# mp3triggerv3.net
KiCad netlist of a schematic drawn in EAGLE
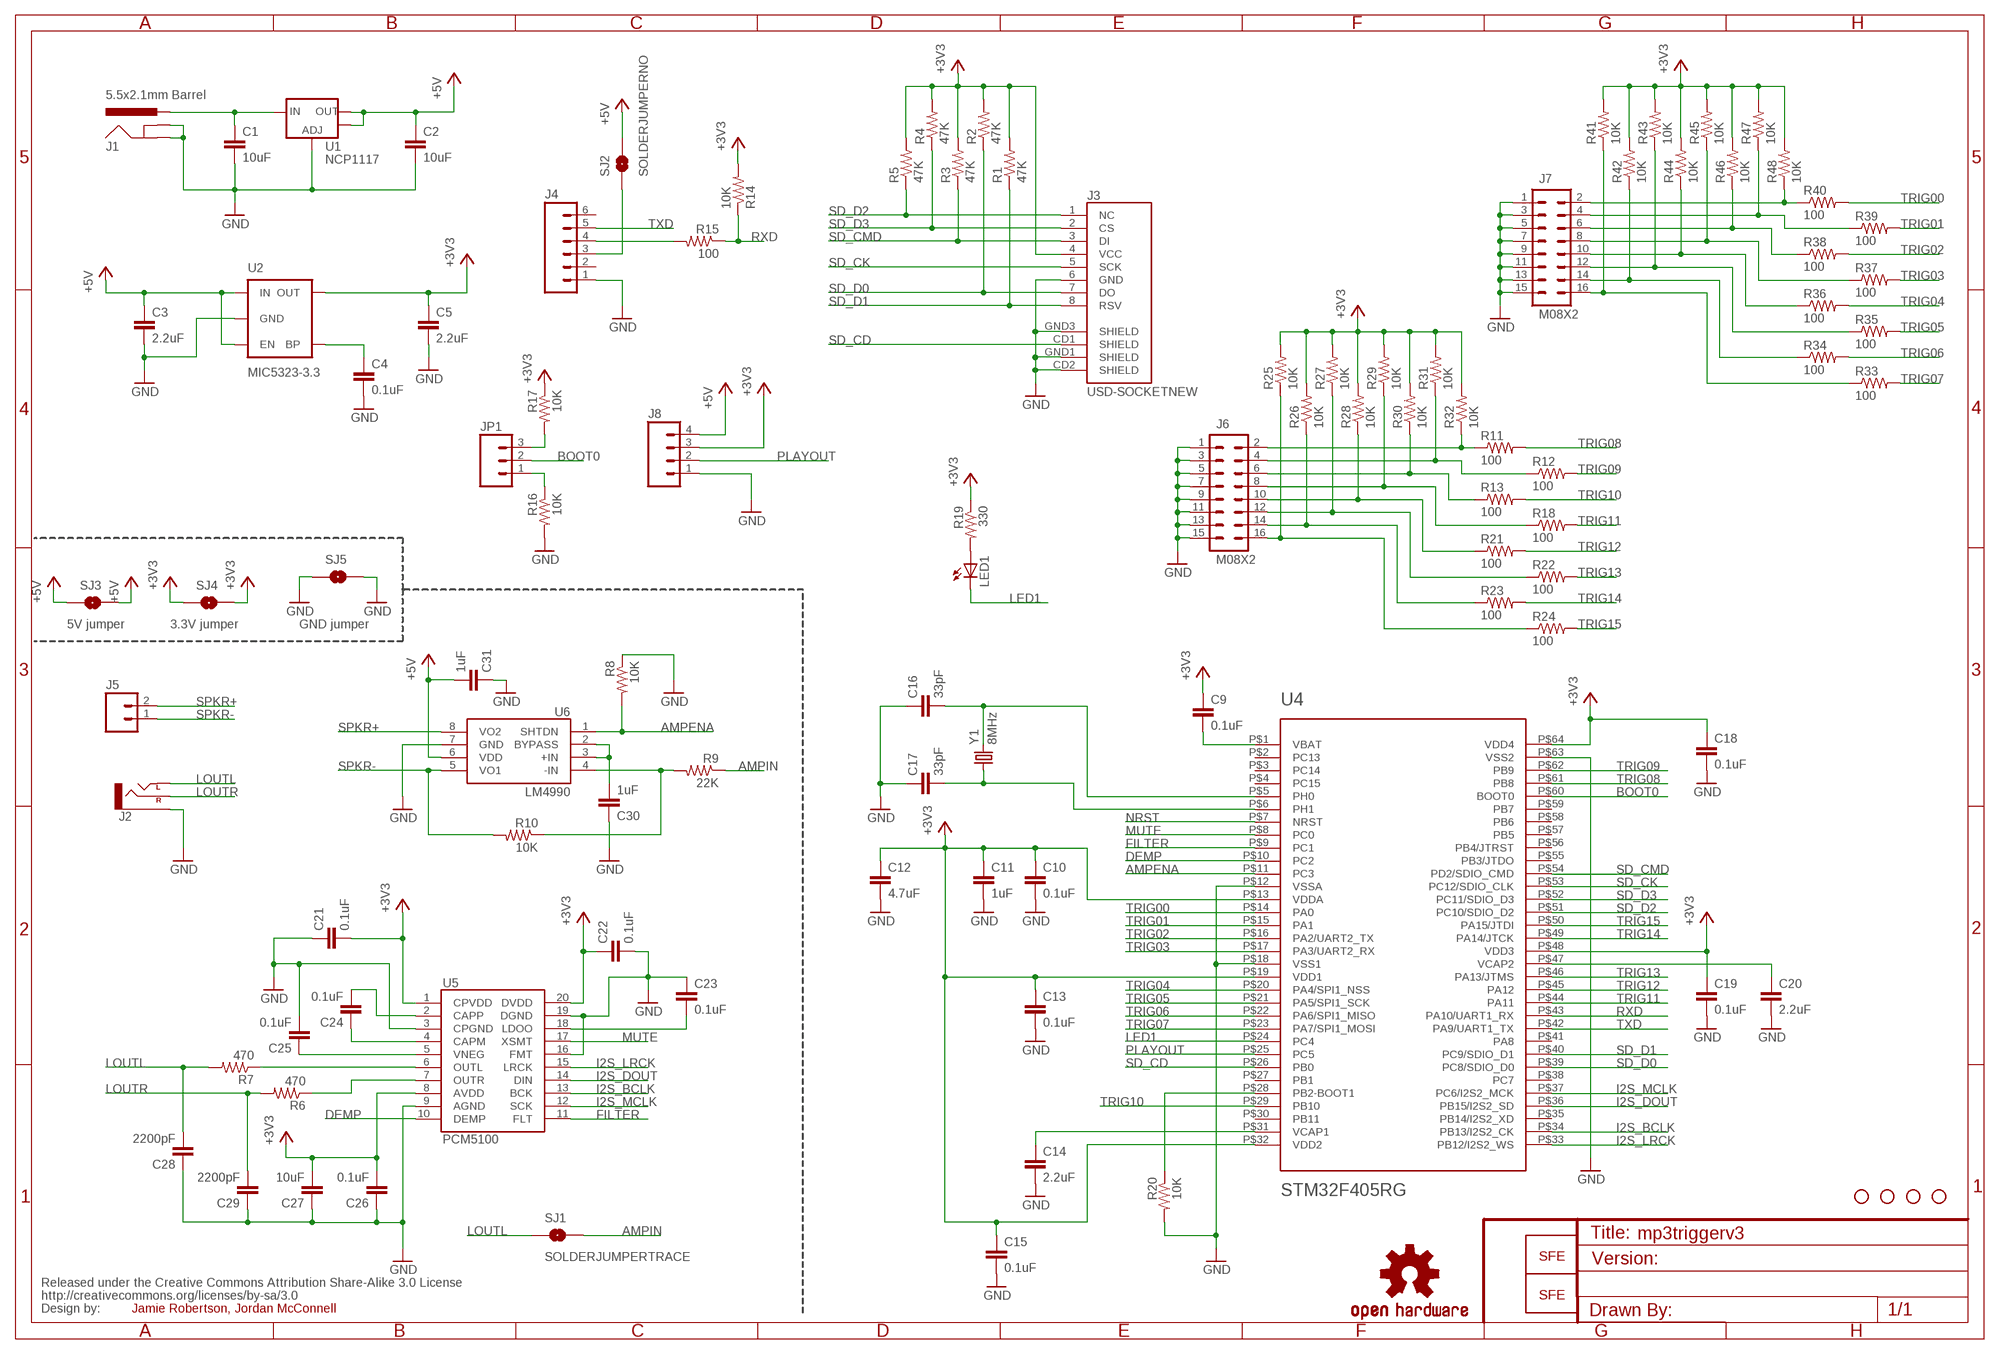
[diagram p0: schematic, sheet 1]

(export (version "E")
  (design (tool "Eeschema 10.0.6"))
  (components
    (comp (ref "C1")
      (value "10uF")
      (footprint "eagle-import:1210")
      (libsource (lib "eagle-import") (part "10UF50V20%(1210)"))
    )
    (comp (ref "C2")
      (value "10uF")
      (footprint "eagle-import:0805")
      (libsource (lib "eagle-import") (part "1UF-25V-10%(0805)"))
    )
    (comp (ref "C3")
      (value "2.2uF")
      (footprint "eagle-import:0805")
      (libsource (lib "eagle-import") (part "1UF-25V-10%(0805)"))
    )
    (comp (ref "C4")
      (value "0.1uF")
      (footprint "eagle-import:0603-CAP")
      (libsource (lib "eagle-import") (part "CAP0603-CAP"))
    )
    (comp (ref "C5")
      (value "2.2uF")
      (footprint "eagle-import:0805")
      (libsource (lib "eagle-import") (part "1UF-25V-10%(0805)"))
    )
    (comp (ref "C9")
      (value "0.1uF")
      (footprint "eagle-import:0603-CAP")
      (libsource (lib "eagle-import") (part "CAP0603-CAP"))
    )
    (comp (ref "C10")
      (value "0.1uF")
      (footprint "eagle-import:0603-CAP")
      (libsource (lib "eagle-import") (part "CAP0603-CAP"))
    )
    (comp (ref "C11")
      (value "1uF")
      (footprint "eagle-import:0603-CAP")
      (libsource (lib "eagle-import") (part "CAP0603-CAP"))
    )
    (comp (ref "C12")
      (value "4.7uF")
      (footprint "eagle-import:0603-CAP")
      (libsource (lib "eagle-import") (part "CAP0603-CAP"))
    )
    (comp (ref "C13")
      (value "0.1uF")
      (footprint "eagle-import:0603-CAP")
      (libsource (lib "eagle-import") (part "CAP0603-CAP"))
    )
    (comp (ref "C14")
      (value "2.2uF")
      (footprint "eagle-import:0603-CAP")
      (libsource (lib "eagle-import") (part "CAP0603-CAP"))
    )
    (comp (ref "C15")
      (value "0.1uF")
      (footprint "eagle-import:0603-CAP")
      (libsource (lib "eagle-import") (part "CAP0603-CAP"))
    )
    (comp (ref "C16")
      (value "33pF")
      (footprint "eagle-import:0603-CAP")
      (libsource (lib "eagle-import") (part "CAP0603-CAP"))
    )
    (comp (ref "C17")
      (value "33pF")
      (footprint "eagle-import:0603-CAP")
      (libsource (lib "eagle-import") (part "CAP0603-CAP"))
    )
    (comp (ref "C18")
      (value "0.1uF")
      (footprint "eagle-import:0603-CAP")
      (libsource (lib "eagle-import") (part "CAP0603-CAP"))
    )
    (comp (ref "C19")
      (value "0.1uF")
      (footprint "eagle-import:0603-CAP")
      (libsource (lib "eagle-import") (part "CAP0603-CAP"))
    )
    (comp (ref "C20")
      (value "2.2uF")
      (footprint "eagle-import:0603-CAP")
      (libsource (lib "eagle-import") (part "CAP0603-CAP"))
    )
    (comp (ref "C21")
      (value "0.1uF")
      (footprint "eagle-import:0603-CAP")
      (libsource (lib "eagle-import") (part "CAP0603-CAP"))
    )
    (comp (ref "C22")
      (value "0.1uF")
      (footprint "eagle-import:0603-CAP")
      (libsource (lib "eagle-import") (part "CAP0603-CAP"))
    )
    (comp (ref "C23")
      (value "0.1uF")
      (footprint "eagle-import:0603-CAP")
      (libsource (lib "eagle-import") (part "CAP0603-CAP"))
    )
    (comp (ref "C24")
      (value "0.1uF")
      (footprint "eagle-import:0603-CAP")
      (libsource (lib "eagle-import") (part "CAP0603-CAP"))
    )
    (comp (ref "C25")
      (value "0.1uF")
      (footprint "eagle-import:0603-CAP")
      (libsource (lib "eagle-import") (part "CAP0603-CAP"))
    )
    (comp (ref "C26")
      (value "0.1uF")
      (footprint "eagle-import:0603-CAP")
      (libsource (lib "eagle-import") (part "CAP0603-CAP"))
    )
    (comp (ref "C27")
      (value "10uF")
      (footprint "eagle-import:0603-CAP")
      (libsource (lib "eagle-import") (part "CAP0603-CAP"))
    )
    (comp (ref "C28")
      (value "2200pF")
      (footprint "eagle-import:0603-CAP")
      (libsource (lib "eagle-import") (part "CAP0603-CAP"))
    )
    (comp (ref "C29")
      (value "2200pF")
      (footprint "eagle-import:0603-CAP")
      (libsource (lib "eagle-import") (part "CAP0603-CAP"))
    )
    (comp (ref "C30")
      (value "1uF")
      (footprint "eagle-import:0603-CAP")
      (libsource (lib "eagle-import") (part "CAP0603-CAP"))
    )
    (comp (ref "C31")
      (value "1uF")
      (footprint "eagle-import:0603-CAP")
      (libsource (lib "eagle-import") (part "CAP0603-CAP"))
    )
    (comp (ref "CC_TEXT1")
      (value "CREATIVE_COMMONS")
      (footprint "eagle-import:CREATIVE_COMMONS")
      (libsource (lib "eagle-import") (part "CREATIVE_COMMONS"))
    )
    (comp (ref "J1")
      (value "5.5x2.1mm Barrel")
      (footprint "eagle-import:POWER_JACK_SMD")
      (libsource (lib "eagle-import") (part "POWER_JACKSMD"))
    )
    (comp (ref "J2")
      (value "AUDIO-JACKSMD2")
      (footprint "eagle-import:AUDIO-JACK-3.5MM-SMD")
      (libsource (lib "eagle-import") (part "AUDIO-JACKSMD2"))
    )
    (comp (ref "J3")
      (value "USD-SOCKETNEW")
      (footprint "eagle-import:MICRO-SD-SOCKET-PP")
      (libsource (lib "eagle-import") (part "USD-SOCKETNEW"))
    )
    (comp (ref "J4")
      (value "M06SIP")
      (footprint "eagle-import:1X06")
      (libsource (lib "eagle-import") (part "M06SIP"))
    )
    (comp (ref "J5")
      (value "M02PTH")
      (footprint "eagle-import:1X02")
      (libsource (lib "eagle-import") (part "M02PTH"))
    )
    (comp (ref "J6")
      (value "M08X2")
      (footprint "eagle-import:2X8")
      (libsource (lib "eagle-import") (part "M08X2"))
    )
    (comp (ref "J7")
      (value "M08X2")
      (footprint "eagle-import:2X8")
      (libsource (lib "eagle-import") (part "M08X2"))
    )
    (comp (ref "J8")
      (value "M04PTH")
      (footprint "eagle-import:1X04")
      (libsource (lib "eagle-import") (part "M04PTH"))
    )
    (comp (ref "JP1")
      (value "M03PTH")
      (footprint "eagle-import:1X03")
      (libsource (lib "eagle-import") (part "M03PTH"))
    )
    (comp (ref "LED1")
      (value "LED0603")
      (footprint "eagle-import:LED-0603")
      (libsource (lib "eagle-import") (part "LED0603"))
    )
    (comp (ref "LOGO1")
      (value "OSHW-LOGOL")
      (footprint "eagle-import:OSHW-LOGO-L")
      (libsource (lib "eagle-import") (part "OSHW-LOGOL"))
    )
    (comp (ref "LOGO2")
      (value "LOGO-SFENEW")
      (footprint "eagle-import:SFE-NEW-WEBLOGO")
      (libsource (lib "eagle-import") (part "LOGO-SFENEW"))
    )
    (comp (ref "LOGO3")
      (value "LOGO-SFESK")
      (footprint "eagle-import:SFE-LOGO-FLAME")
      (libsource (lib "eagle-import") (part "LOGO-SFESK"))
    )
    (comp (ref "R1")
      (value "47K")
      (footprint "eagle-import:0603-RES")
      (libsource (lib "eagle-import") (part "RESISTOR0603-RES"))
    )
    (comp (ref "R2")
      (value "47K")
      (footprint "eagle-import:0603-RES")
      (libsource (lib "eagle-import") (part "RESISTOR0603-RES"))
    )
    (comp (ref "R3")
      (value "47K")
      (footprint "eagle-import:0603-RES")
      (libsource (lib "eagle-import") (part "RESISTOR0603-RES"))
    )
    (comp (ref "R4")
      (value "47K")
      (footprint "eagle-import:0603-RES")
      (libsource (lib "eagle-import") (part "RESISTOR0603-RES"))
    )
    (comp (ref "R5")
      (value "47K")
      (footprint "eagle-import:0603-RES")
      (libsource (lib "eagle-import") (part "RESISTOR0603-RES"))
    )
    (comp (ref "R6")
      (value "470")
      (footprint "eagle-import:0603-RES")
      (libsource (lib "eagle-import") (part "RESISTOR0603-RES"))
    )
    (comp (ref "R7")
      (value "470")
      (footprint "eagle-import:0603-RES")
      (libsource (lib "eagle-import") (part "RESISTOR0603-RES"))
    )
    (comp (ref "R8")
      (value "10K")
      (footprint "eagle-import:0603-RES")
      (libsource (lib "eagle-import") (part "RESISTOR0603-RES"))
    )
    (comp (ref "R9")
      (value "22K")
      (footprint "eagle-import:0603-RES")
      (libsource (lib "eagle-import") (part "RESISTOR0603-RES"))
    )
    (comp (ref "R10")
      (value "10K")
      (footprint "eagle-import:0603-RES")
      (libsource (lib "eagle-import") (part "RESISTOR0603-RES"))
    )
    (comp (ref "R11")
      (value "100")
      (footprint "eagle-import:0603-RES")
      (libsource (lib "eagle-import") (part "RESISTOR0603-RES"))
    )
    (comp (ref "R12")
      (value "100")
      (footprint "eagle-import:0603-RES")
      (libsource (lib "eagle-import") (part "RESISTOR0603-RES"))
    )
    (comp (ref "R13")
      (value "100")
      (footprint "eagle-import:0603-RES")
      (libsource (lib "eagle-import") (part "RESISTOR0603-RES"))
    )
    (comp (ref "R14")
      (value "10K")
      (footprint "eagle-import:0603-RES")
      (libsource (lib "eagle-import") (part "RESISTOR0603-RES"))
    )
    (comp (ref "R15")
      (value "100")
      (footprint "eagle-import:0603-RES")
      (libsource (lib "eagle-import") (part "RESISTOR0603-RES"))
    )
    (comp (ref "R16")
      (value "10K")
      (footprint "eagle-import:0603-RES")
      (libsource (lib "eagle-import") (part "RESISTOR0603-RES"))
    )
    (comp (ref "R17")
      (value "10K")
      (footprint "eagle-import:0603-RES")
      (libsource (lib "eagle-import") (part "RESISTOR0603-RES"))
    )
    (comp (ref "R18")
      (value "100")
      (footprint "eagle-import:0603-RES")
      (libsource (lib "eagle-import") (part "RESISTOR0603-RES"))
    )
    (comp (ref "R19")
      (value "330")
      (footprint "eagle-import:0603-RES")
      (libsource (lib "eagle-import") (part "RESISTOR0603-RES"))
    )
    (comp (ref "R20")
      (value "10K")
      (footprint "eagle-import:0603-RES")
      (libsource (lib "eagle-import") (part "RESISTOR0603-RES"))
    )
    (comp (ref "R21")
      (value "100")
      (footprint "eagle-import:0603-RES")
      (libsource (lib "eagle-import") (part "RESISTOR0603-RES"))
    )
    (comp (ref "R22")
      (value "100")
      (footprint "eagle-import:0603-RES")
      (libsource (lib "eagle-import") (part "RESISTOR0603-RES"))
    )
    (comp (ref "R23")
      (value "100")
      (footprint "eagle-import:0603-RES")
      (libsource (lib "eagle-import") (part "RESISTOR0603-RES"))
    )
    (comp (ref "R24")
      (value "100")
      (footprint "eagle-import:0603-RES")
      (libsource (lib "eagle-import") (part "RESISTOR0603-RES"))
    )
    (comp (ref "R25")
      (value "10K")
      (footprint "eagle-import:0603-RES")
      (libsource (lib "eagle-import") (part "RESISTOR0603-RES"))
    )
    (comp (ref "R26")
      (value "10K")
      (footprint "eagle-import:0603-RES")
      (libsource (lib "eagle-import") (part "RESISTOR0603-RES"))
    )
    (comp (ref "R27")
      (value "10K")
      (footprint "eagle-import:0603-RES")
      (libsource (lib "eagle-import") (part "RESISTOR0603-RES"))
    )
    (comp (ref "R28")
      (value "10K")
      (footprint "eagle-import:0603-RES")
      (libsource (lib "eagle-import") (part "RESISTOR0603-RES"))
    )
    (comp (ref "R29")
      (value "10K")
      (footprint "eagle-import:0603-RES")
      (libsource (lib "eagle-import") (part "RESISTOR0603-RES"))
    )
    (comp (ref "R30")
      (value "10K")
      (footprint "eagle-import:0603-RES")
      (libsource (lib "eagle-import") (part "RESISTOR0603-RES"))
    )
    (comp (ref "R31")
      (value "10K")
      (footprint "eagle-import:0603-RES")
      (libsource (lib "eagle-import") (part "RESISTOR0603-RES"))
    )
    (comp (ref "R32")
      (value "10K")
      (footprint "eagle-import:0603-RES")
      (libsource (lib "eagle-import") (part "RESISTOR0603-RES"))
    )
    (comp (ref "R33")
      (value "100")
      (footprint "eagle-import:0603-RES")
      (libsource (lib "eagle-import") (part "RESISTOR0603-RES"))
    )
    (comp (ref "R34")
      (value "100")
      (footprint "eagle-import:0603-RES")
      (libsource (lib "eagle-import") (part "RESISTOR0603-RES"))
    )
    (comp (ref "R35")
      (value "100")
      (footprint "eagle-import:0603-RES")
      (libsource (lib "eagle-import") (part "RESISTOR0603-RES"))
    )
    (comp (ref "R36")
      (value "100")
      (footprint "eagle-import:0603-RES")
      (libsource (lib "eagle-import") (part "RESISTOR0603-RES"))
    )
    (comp (ref "R37")
      (value "100")
      (footprint "eagle-import:0603-RES")
      (libsource (lib "eagle-import") (part "RESISTOR0603-RES"))
    )
    (comp (ref "R38")
      (value "100")
      (footprint "eagle-import:0603-RES")
      (libsource (lib "eagle-import") (part "RESISTOR0603-RES"))
    )
    (comp (ref "R39")
      (value "100")
      (footprint "eagle-import:0603-RES")
      (libsource (lib "eagle-import") (part "RESISTOR0603-RES"))
    )
    (comp (ref "R40")
      (value "100")
      (footprint "eagle-import:0603-RES")
      (libsource (lib "eagle-import") (part "RESISTOR0603-RES"))
    )
    (comp (ref "R41")
      (value "10K")
      (footprint "eagle-import:0603-RES")
      (libsource (lib "eagle-import") (part "RESISTOR0603-RES"))
    )
    (comp (ref "R42")
      (value "10K")
      (footprint "eagle-import:0603-RES")
      (libsource (lib "eagle-import") (part "RESISTOR0603-RES"))
    )
    (comp (ref "R43")
      (value "10K")
      (footprint "eagle-import:0603-RES")
      (libsource (lib "eagle-import") (part "RESISTOR0603-RES"))
    )
    (comp (ref "R44")
      (value "10K")
      (footprint "eagle-import:0603-RES")
      (libsource (lib "eagle-import") (part "RESISTOR0603-RES"))
    )
    (comp (ref "R45")
      (value "10K")
      (footprint "eagle-import:0603-RES")
      (libsource (lib "eagle-import") (part "RESISTOR0603-RES"))
    )
    (comp (ref "R46")
      (value "10K")
      (footprint "eagle-import:0603-RES")
      (libsource (lib "eagle-import") (part "RESISTOR0603-RES"))
    )
    (comp (ref "R47")
      (value "10K")
      (footprint "eagle-import:0603-RES")
      (libsource (lib "eagle-import") (part "RESISTOR0603-RES"))
    )
    (comp (ref "R48")
      (value "10K")
      (footprint "eagle-import:0603-RES")
      (libsource (lib "eagle-import") (part "RESISTOR0603-RES"))
    )
    (comp (ref "SJ1")
      (value "SOLDERJUMPERTRACE")
      (footprint "eagle-import:SJ_2S-TRACE")
      (libsource (lib "eagle-import") (part "SOLDERJUMPERTRACE"))
    )
    (comp (ref "SJ2")
      (value "SOLDERJUMPERNO")
      (footprint "eagle-import:SJ_2S-NO")
      (libsource (lib "eagle-import") (part "SOLDERJUMPERNO"))
    )
    (comp (ref "SJ3")
      (value "SOLDERJUMPERTRACE")
      (footprint "eagle-import:SJ_2S-TRACE")
      (libsource (lib "eagle-import") (part "SOLDERJUMPERTRACE"))
    )
    (comp (ref "SJ4")
      (value "SOLDERJUMPERTRACE")
      (footprint "eagle-import:SJ_2S-TRACE")
      (libsource (lib "eagle-import") (part "SOLDERJUMPERTRACE"))
    )
    (comp (ref "SJ5")
      (value "SOLDERJUMPERTRACE")
      (footprint "eagle-import:SJ_2S-TRACE")
      (libsource (lib "eagle-import") (part "SOLDERJUMPERTRACE"))
    )
    (comp (ref "STANDOFF1")
      (value "STAND-OFF")
      (footprint "eagle-import:STAND-OFF")
      (libsource (lib "eagle-import") (part "STAND-OFF"))
    )
    (comp (ref "STANDOFF2")
      (value "STAND-OFF")
      (footprint "eagle-import:STAND-OFF")
      (libsource (lib "eagle-import") (part "STAND-OFF"))
    )
    (comp (ref "STANDOFF3")
      (value "STAND-OFF")
      (footprint "eagle-import:STAND-OFF")
      (libsource (lib "eagle-import") (part "STAND-OFF"))
    )
    (comp (ref "STANDOFF4")
      (value "STAND-OFF")
      (footprint "eagle-import:STAND-OFF")
      (libsource (lib "eagle-import") (part "STAND-OFF"))
    )
    (comp (ref "U1")
      (value "NCP1117")
      (footprint "eagle-import:SOT223")
      (libsource (lib "eagle-import") (part "V_REG_LM1117SOT223"))
    )
    (comp (ref "U2")
      (value "MIC5323-3.3")
      (footprint "eagle-import:SOT23-5")
      (libsource (lib "eagle-import") (part "MIC52053.3V"))
    )
    (comp (ref "U4")
      (value "STM32F405RG")
      (footprint "eagle-import:TQFP-10X10-64")
      (libsource (lib "eagle-import") (part "STM32F405RG"))
    )
    (comp (ref "U5")
      (value "PCM5100")
      (footprint "eagle-import:PW_R-PDSO-G20")
      (libsource (lib "eagle-import") (part "PCM5100"))
    )
    (comp (ref "U6")
      (value "LM4990")
      (footprint "eagle-import:S-PDSO-G08")
      (libsource (lib "eagle-import") (part "LM4990"))
    )
    (comp (ref "Y1")
      (value "8MHz")
      (footprint "eagle-import:HC49UP")
      (libsource (lib "eagle-import") (part "CRYSTALSMD"))
    )
  )
  (nets
    (net (code "1") (name "+3V3") (class "Default")
      (node (ref "C10") (pin "1") (pinfunction "1_1") (pintype "passive"))
      (node (ref "C11") (pin "1") (pinfunction "1_1") (pintype "passive"))
      (node (ref "C12") (pin "1") (pinfunction "1_1") (pintype "passive"))
      (node (ref "C13") (pin "1") (pinfunction "1_1") (pintype "passive"))
      (node (ref "C15") (pin "1") (pinfunction "1_1") (pintype "passive"))
      (node (ref "C18") (pin "1") (pinfunction "1_1") (pintype "passive"))
      (node (ref "C19") (pin "1") (pinfunction "1_1") (pintype "passive"))
      (node (ref "C21") (pin "2") (pinfunction "2_2") (pintype "passive"))
      (node (ref "C22") (pin "1") (pinfunction "1_1") (pintype "passive"))
      (node (ref "C26") (pin "2") (pinfunction "2_2") (pintype "passive"))
      (node (ref "C27") (pin "2") (pinfunction "2_2") (pintype "passive"))
      (node (ref "C5") (pin "1") (pinfunction "1_1") (pintype "passive"))
      (node (ref "C9") (pin "1") (pinfunction "1_1") (pintype "passive"))
      (node (ref "J3") (pin "4") (pinfunction "VCC_4") (pintype "bidirectional"))
      (node (ref "J8") (pin "3") (pinfunction "3_3") (pintype "passive"))
      (node (ref "R1") (pin "2") (pinfunction "2_2") (pintype "passive"))
      (node (ref "R14") (pin "2") (pinfunction "2_2") (pintype "passive"))
      (node (ref "R17") (pin "1") (pinfunction "1_1") (pintype "passive"))
      (node (ref "R19") (pin "1") (pinfunction "1_1") (pintype "passive"))
      (node (ref "R2") (pin "2") (pinfunction "2_2") (pintype "passive"))
      (node (ref "R25") (pin "2") (pinfunction "2_2") (pintype "passive"))
      (node (ref "R26") (pin "2") (pinfunction "2_2") (pintype "passive"))
      (node (ref "R27") (pin "2") (pinfunction "2_2") (pintype "passive"))
      (node (ref "R28") (pin "2") (pinfunction "2_2") (pintype "passive"))
      (node (ref "R29") (pin "2") (pinfunction "2_2") (pintype "passive"))
      (node (ref "R3") (pin "2") (pinfunction "2_2") (pintype "passive"))
      (node (ref "R30") (pin "2") (pinfunction "2_2") (pintype "passive"))
      (node (ref "R31") (pin "2") (pinfunction "2_2") (pintype "passive"))
      (node (ref "R32") (pin "2") (pinfunction "2_2") (pintype "passive"))
      (node (ref "R4") (pin "2") (pinfunction "2_2") (pintype "passive"))
      (node (ref "R41") (pin "2") (pinfunction "2_2") (pintype "passive"))
      (node (ref "R42") (pin "2") (pinfunction "2_2") (pintype "passive"))
      (node (ref "R43") (pin "2") (pinfunction "2_2") (pintype "passive"))
      (node (ref "R44") (pin "2") (pinfunction "2_2") (pintype "passive"))
      (node (ref "R45") (pin "2") (pinfunction "2_2") (pintype "passive"))
      (node (ref "R46") (pin "2") (pinfunction "2_2") (pintype "passive"))
      (node (ref "R47") (pin "2") (pinfunction "2_2") (pintype "passive"))
      (node (ref "R48") (pin "2") (pinfunction "2_2") (pintype "passive"))
      (node (ref "R5") (pin "2") (pinfunction "2_2") (pintype "passive"))
      (node (ref "SJ4") (pin "1") (pinfunction "1_1") (pintype "passive"))
      (node (ref "SJ4") (pin "2") (pinfunction "2_2") (pintype "passive"))
      (node (ref "U2") (pin "5") (pinfunction "OUT_5") (pintype "passive"))
      (node (ref "U4") (pin "P$13") (pinfunction "VDDA_P$13") (pintype "bidirectional"))
      (node (ref "U4") (pin "P$19") (pinfunction "VDD1_P$19") (pintype "bidirectional"))
      (node (ref "U4") (pin "P$32") (pinfunction "VDD2_P$32") (pintype "bidirectional"))
      (node (ref "U4") (pin "P$48") (pinfunction "VDD3_P$48") (pintype "bidirectional"))
      (node (ref "U4") (pin "P$64") (pinfunction "VDD4_P$64") (pintype "bidirectional"))
      (node (ref "U5") (pin "1") (pinfunction "CPVDD_1") (pintype "bidirectional"))
      (node (ref "U5") (pin "20") (pinfunction "DVDD_20") (pintype "bidirectional"))
      (node (ref "U5") (pin "8") (pinfunction "AVDD_8") (pintype "bidirectional"))
    )
    (net (code "2") (name "+5V") (class "Default")
      (node (ref "C2") (pin "1") (pinfunction "1_1") (pintype "passive"))
      (node (ref "C3") (pin "1") (pinfunction "1_1") (pintype "passive"))
      (node (ref "C31") (pin "2") (pinfunction "2_2") (pintype "passive"))
      (node (ref "J8") (pin "4") (pinfunction "4_4") (pintype "passive"))
      (node (ref "SJ2") (pin "2") (pinfunction "2_2") (pintype "passive"))
      (node (ref "SJ3") (pin "1") (pinfunction "1_1") (pintype "passive"))
      (node (ref "SJ3") (pin "2") (pinfunction "2_2") (pintype "passive"))
      (node (ref "U1") (pin "2") (pinfunction "OUT_2") (pintype "output"))
      (node (ref "U1") (pin "4") (pinfunction "OUT_4") (pintype "output"))
      (node (ref "U2") (pin "1") (pinfunction "IN_1") (pintype "input"))
      (node (ref "U2") (pin "3") (pinfunction "EN_3") (pintype "input"))
      (node (ref "U6") (pin "6") (pinfunction "VDD_6") (pintype "bidirectional"))
    )
    (net (code "3") (name "/AMPENA") (class "Default")
      (node (ref "R8") (pin "2") (pinfunction "2_2") (pintype "passive"))
      (node (ref "U4") (pin "P$11") (pinfunction "PC3_P$11") (pintype "bidirectional"))
      (node (ref "U6") (pin "1") (pinfunction "SHTDN_1") (pintype "bidirectional"))
    )
    (net (code "4") (name "/AMPIN") (class "Default")
      (node (ref "R9") (pin "1") (pinfunction "1_1") (pintype "passive"))
      (node (ref "SJ1") (pin "2") (pinfunction "2_2") (pintype "passive"))
    )
    (net (code "5") (name "/BOOT0") (class "Default")
      (node (ref "JP1") (pin "2") (pinfunction "2_2") (pintype "passive"))
      (node (ref "U4") (pin "P$60") (pinfunction "BOOT0_P$60") (pintype "bidirectional"))
    )
    (net (code "6") (name "/DEMP") (class "Default")
      (node (ref "U4") (pin "P$10") (pinfunction "PC2_P$10") (pintype "bidirectional"))
      (node (ref "U5") (pin "10") (pinfunction "DEMP_10") (pintype "bidirectional"))
    )
    (net (code "7") (name "/FILTER") (class "Default")
      (node (ref "U4") (pin "P$9") (pinfunction "PC1_P$9") (pintype "bidirectional"))
      (node (ref "U5") (pin "11") (pinfunction "FLT_11") (pintype "bidirectional"))
    )
    (net (code "8") (name "/I2S_BCLK") (class "Default")
      (node (ref "U4") (pin "P$34") (pinfunction "PB13/I2S2_CK_P$34") (pintype "bidirectional"))
      (node (ref "U5") (pin "13") (pinfunction "BCK_13") (pintype "bidirectional"))
    )
    (net (code "9") (name "/I2S_DOUT") (class "Default")
      (node (ref "U4") (pin "P$36") (pinfunction "PB15/I2S2_SD_P$36") (pintype "bidirectional"))
      (node (ref "U5") (pin "14") (pinfunction "DIN_14") (pintype "bidirectional"))
    )
    (net (code "10") (name "/I2S_LRCK") (class "Default")
      (node (ref "U4") (pin "P$33") (pinfunction "PB12/I2S2_WS_P$33") (pintype "bidirectional"))
      (node (ref "U5") (pin "15") (pinfunction "LRCK_15") (pintype "bidirectional"))
    )
    (net (code "11") (name "/I2S_MCLK") (class "Default")
      (node (ref "U4") (pin "P$37") (pinfunction "PC6/I2S2_MCK_P$37") (pintype "bidirectional"))
      (node (ref "U5") (pin "12") (pinfunction "SCK_12") (pintype "bidirectional"))
    )
    (net (code "12") (name "/LED1") (class "Default")
      (node (ref "LED1") (pin "C") (pinfunction "C_C") (pintype "passive"))
      (node (ref "U4") (pin "P$24") (pinfunction "PC4_P$24") (pintype "bidirectional"))
    )
    (net (code "13") (name "/LOUTL") (class "Default")
      (node (ref "C28") (pin "2") (pinfunction "2_2") (pintype "passive"))
      (node (ref "J2") (pin "TIP") (pinfunction "LEFT_TIP") (pintype "bidirectional"))
      (node (ref "R7") (pin "2") (pinfunction "2_2") (pintype "passive"))
      (node (ref "SJ1") (pin "1") (pinfunction "1_1") (pintype "passive"))
    )
    (net (code "14") (name "/LOUTR") (class "Default")
      (node (ref "C29") (pin "2") (pinfunction "2_2") (pintype "passive"))
      (node (ref "J2") (pin "RING") (pinfunction "RIGHT_RING") (pintype "bidirectional"))
      (node (ref "R6") (pin "2") (pinfunction "2_2") (pintype "passive"))
    )
    (net (code "15") (name "/MUTE") (class "Default")
      (node (ref "U4") (pin "P$8") (pinfunction "PC0_P$8") (pintype "bidirectional"))
      (node (ref "U5") (pin "17") (pinfunction "XSMT_17") (pintype "bidirectional"))
    )
    (net (code "16") (name "/NRST") (class "Default")
      (node (ref "U4") (pin "P$7") (pinfunction "NRST_P$7") (pintype "bidirectional"))
    )
    (net (code "17") (name "/PLAYOUT") (class "Default")
      (node (ref "J8") (pin "2") (pinfunction "2_2") (pintype "passive"))
      (node (ref "U4") (pin "P$25") (pinfunction "PC5_P$25") (pintype "bidirectional"))
    )
    (net (code "18") (name "/RXD") (class "Default")
      (node (ref "R14") (pin "1") (pinfunction "1_1") (pintype "passive"))
      (node (ref "R15") (pin "1") (pinfunction "1_1") (pintype "passive"))
      (node (ref "U4") (pin "P$43") (pinfunction "PA10/UART1_RX_P$43") (pintype "bidirectional"))
    )
    (net (code "19") (name "/SD_CD") (class "Default")
      (node (ref "J3") (pin "CD1") (pinfunction "SHIELD_CD1") (pintype "bidirectional"))
      (node (ref "U4") (pin "P$26") (pinfunction "PB0_P$26") (pintype "bidirectional"))
    )
    (net (code "20") (name "/SD_CK") (class "Default")
      (node (ref "J3") (pin "5") (pinfunction "SCK_5") (pintype "bidirectional"))
      (node (ref "U4") (pin "P$53") (pinfunction "PC12/SDIO_CLK_P$53") (pintype "bidirectional"))
    )
    (net (code "21") (name "/SD_CMD") (class "Default")
      (node (ref "J3") (pin "3") (pinfunction "DI_3") (pintype "bidirectional"))
      (node (ref "R3") (pin "1") (pinfunction "1_1") (pintype "passive"))
      (node (ref "U4") (pin "P$54") (pinfunction "PD2/SDIO_CMD_P$54") (pintype "bidirectional"))
    )
    (net (code "22") (name "/SD_D0") (class "Default")
      (node (ref "J3") (pin "7") (pinfunction "DO_7") (pintype "bidirectional"))
      (node (ref "R2") (pin "1") (pinfunction "1_1") (pintype "passive"))
      (node (ref "U4") (pin "P$39") (pinfunction "PC8/SDIO_D0_P$39") (pintype "bidirectional"))
    )
    (net (code "23") (name "/SD_D1") (class "Default")
      (node (ref "J3") (pin "8") (pinfunction "RSV_8") (pintype "bidirectional"))
      (node (ref "R1") (pin "1") (pinfunction "1_1") (pintype "passive"))
      (node (ref "U4") (pin "P$40") (pinfunction "PC9/SDIO_D1_P$40") (pintype "bidirectional"))
    )
    (net (code "24") (name "/SD_D2") (class "Default")
      (node (ref "J3") (pin "1") (pinfunction "NC_1") (pintype "bidirectional"))
      (node (ref "R5") (pin "1") (pinfunction "1_1") (pintype "passive"))
      (node (ref "U4") (pin "P$51") (pinfunction "PC10/SDIO_D2_P$51") (pintype "bidirectional"))
    )
    (net (code "25") (name "/SD_D3") (class "Default")
      (node (ref "J3") (pin "2") (pinfunction "CS_2") (pintype "bidirectional"))
      (node (ref "R4") (pin "1") (pinfunction "1_1") (pintype "passive"))
      (node (ref "U4") (pin "P$52") (pinfunction "PC11/SDIO_D3_P$52") (pintype "bidirectional"))
    )
    (net (code "26") (name "/SPKR+") (class "Default")
      (node (ref "J5") (pin "2") (pinfunction "2_2") (pintype "passive"))
      (node (ref "U6") (pin "8") (pinfunction "VO2_8") (pintype "bidirectional"))
    )
    (net (code "27") (name "/SPKR-") (class "Default")
      (node (ref "J5") (pin "1") (pinfunction "1_1") (pintype "passive"))
      (node (ref "R10") (pin "2") (pinfunction "2_2") (pintype "passive"))
      (node (ref "U6") (pin "5") (pinfunction "VO1_5") (pintype "bidirectional"))
    )
    (net (code "28") (name "/TRIG00") (class "Default")
      (node (ref "R40") (pin "2") (pinfunction "2_2") (pintype "passive"))
      (node (ref "U4") (pin "P$14") (pinfunction "PA0_P$14") (pintype "bidirectional"))
    )
    (net (code "29") (name "/TRIG01") (class "Default")
      (node (ref "R39") (pin "2") (pinfunction "2_2") (pintype "passive"))
      (node (ref "U4") (pin "P$15") (pinfunction "PA1_P$15") (pintype "bidirectional"))
    )
    (net (code "30") (name "/TRIG02") (class "Default")
      (node (ref "R38") (pin "2") (pinfunction "2_2") (pintype "passive"))
      (node (ref "U4") (pin "P$16") (pinfunction "PA2/UART2_TX_P$16") (pintype "bidirectional"))
    )
    (net (code "31") (name "/TRIG03") (class "Default")
      (node (ref "R37") (pin "2") (pinfunction "2_2") (pintype "passive"))
      (node (ref "U4") (pin "P$17") (pinfunction "PA3/UART2_RX_P$17") (pintype "bidirectional"))
    )
    (net (code "32") (name "/TRIG04") (class "Default")
      (node (ref "R36") (pin "2") (pinfunction "2_2") (pintype "passive"))
      (node (ref "U4") (pin "P$20") (pinfunction "PA4/SPI1_NSS_P$20") (pintype "bidirectional"))
    )
    (net (code "33") (name "/TRIG05") (class "Default")
      (node (ref "R35") (pin "2") (pinfunction "2_2") (pintype "passive"))
      (node (ref "U4") (pin "P$21") (pinfunction "PA5/SPI1_SCK_P$21") (pintype "bidirectional"))
    )
    (net (code "34") (name "/TRIG06") (class "Default")
      (node (ref "R34") (pin "2") (pinfunction "2_2") (pintype "passive"))
      (node (ref "U4") (pin "P$22") (pinfunction "PA6/SPI1_MISO_P$22") (pintype "bidirectional"))
    )
    (net (code "35") (name "/TRIG07") (class "Default")
      (node (ref "R33") (pin "2") (pinfunction "2_2") (pintype "passive"))
      (node (ref "U4") (pin "P$23") (pinfunction "PA7/SPI1_MOSI_P$23") (pintype "bidirectional"))
    )
    (net (code "36") (name "/TRIG08") (class "Default")
      (node (ref "R11") (pin "2") (pinfunction "2_2") (pintype "passive"))
      (node (ref "U4") (pin "P$61") (pinfunction "PB8_P$61") (pintype "bidirectional"))
    )
    (net (code "37") (name "/TRIG09") (class "Default")
      (node (ref "R12") (pin "2") (pinfunction "2_2") (pintype "passive"))
      (node (ref "U4") (pin "P$62") (pinfunction "PB9_P$62") (pintype "bidirectional"))
    )
    (net (code "38") (name "/TRIG10") (class "Default")
      (node (ref "R13") (pin "2") (pinfunction "2_2") (pintype "passive"))
      (node (ref "U4") (pin "P$29") (pinfunction "PB10_P$29") (pintype "bidirectional"))
    )
    (net (code "39") (name "/TRIG11") (class "Default")
      (node (ref "R18") (pin "2") (pinfunction "2_2") (pintype "passive"))
      (node (ref "U4") (pin "P$44") (pinfunction "PA11_P$44") (pintype "bidirectional"))
    )
    (net (code "40") (name "/TRIG12") (class "Default")
      (node (ref "R21") (pin "2") (pinfunction "2_2") (pintype "passive"))
      (node (ref "U4") (pin "P$45") (pinfunction "PA12_P$45") (pintype "bidirectional"))
    )
    (net (code "41") (name "/TRIG13") (class "Default")
      (node (ref "R22") (pin "2") (pinfunction "2_2") (pintype "passive"))
      (node (ref "U4") (pin "P$46") (pinfunction "PA13/JTMS_P$46") (pintype "bidirectional"))
    )
    (net (code "42") (name "/TRIG14") (class "Default")
      (node (ref "R23") (pin "2") (pinfunction "2_2") (pintype "passive"))
      (node (ref "U4") (pin "P$49") (pinfunction "PA14/JTCK_P$49") (pintype "bidirectional"))
    )
    (net (code "43") (name "/TRIG15") (class "Default")
      (node (ref "R24") (pin "2") (pinfunction "2_2") (pintype "passive"))
      (node (ref "U4") (pin "P$50") (pinfunction "PA15/JTDI_P$50") (pintype "bidirectional"))
    )
    (net (code "44") (name "/TXD") (class "Default")
      (node (ref "J4") (pin "5") (pinfunction "5_5") (pintype "passive"))
      (node (ref "U4") (pin "P$42") (pinfunction "PA9/UART1_TX_P$42") (pintype "bidirectional"))
    )
    (net (code "45") (name "GND") (class "Default")
      (node (ref "C1") (pin "2") (pinfunction "2_2") (pintype "passive"))
      (node (ref "C10") (pin "2") (pinfunction "2_2") (pintype "passive"))
      (node (ref "C11") (pin "2") (pinfunction "2_2") (pintype "passive"))
      (node (ref "C12") (pin "2") (pinfunction "2_2") (pintype "passive"))
      (node (ref "C13") (pin "2") (pinfunction "2_2") (pintype "passive"))
      (node (ref "C14") (pin "2") (pinfunction "2_2") (pintype "passive"))
      (node (ref "C15") (pin "2") (pinfunction "2_2") (pintype "passive"))
      (node (ref "C16") (pin "1") (pinfunction "1_1") (pintype "passive"))
      (node (ref "C17") (pin "1") (pinfunction "1_1") (pintype "passive"))
      (node (ref "C18") (pin "2") (pinfunction "2_2") (pintype "passive"))
      (node (ref "C19") (pin "2") (pinfunction "2_2") (pintype "passive"))
      (node (ref "C2") (pin "2") (pinfunction "2_2") (pintype "passive"))
      (node (ref "C20") (pin "2") (pinfunction "2_2") (pintype "passive"))
      (node (ref "C21") (pin "1") (pinfunction "1_1") (pintype "passive"))
      (node (ref "C22") (pin "2") (pinfunction "2_2") (pintype "passive"))
      (node (ref "C23") (pin "1") (pinfunction "1_1") (pintype "passive"))
      (node (ref "C25") (pin "2") (pinfunction "2_2") (pintype "passive"))
      (node (ref "C26") (pin "1") (pinfunction "1_1") (pintype "passive"))
      (node (ref "C27") (pin "1") (pinfunction "1_1") (pintype "passive"))
      (node (ref "C28") (pin "1") (pinfunction "1_1") (pintype "passive"))
      (node (ref "C29") (pin "1") (pinfunction "1_1") (pintype "passive"))
      (node (ref "C3") (pin "2") (pinfunction "2_2") (pintype "passive"))
      (node (ref "C30") (pin "1") (pinfunction "1_1") (pintype "passive"))
      (node (ref "C31") (pin "1") (pinfunction "1_1") (pintype "passive"))
      (node (ref "C4") (pin "2") (pinfunction "2_2") (pintype "passive"))
      (node (ref "C5") (pin "2") (pinfunction "2_2") (pintype "passive"))
      (node (ref "J1") (pin "GND") (pinfunction "GNDBREAK_GND") (pintype "bidirectional"))
      (node (ref "J1") (pin "P$4") (pinfunction "GND_P$4") (pintype "bidirectional"))
      (node (ref "J2") (pin "SLEEVE") (pinfunction "SLEEVE_SLEEVE") (pintype "bidirectional"))
      (node (ref "J3") (pin "6") (pinfunction "GND_6") (pintype "bidirectional"))
      (node (ref "J3") (pin "CD2") (pinfunction "SHIELD_CD2") (pintype "bidirectional"))
      (node (ref "J3") (pin "GND1") (pinfunction "SHIELD_GND1") (pintype "bidirectional"))
      (node (ref "J3") (pin "GND3") (pinfunction "SHIELD_GND3") (pintype "bidirectional"))
      (node (ref "J4") (pin "1") (pinfunction "1_1") (pintype "passive"))
      (node (ref "J6") (pin "1") (pinfunction "1_1") (pintype "passive"))
      (node (ref "J6") (pin "11") (pinfunction "11_11") (pintype "passive"))
      (node (ref "J6") (pin "13") (pinfunction "13_13") (pintype "passive"))
      (node (ref "J6") (pin "15") (pinfunction "15_15") (pintype "passive"))
      (node (ref "J6") (pin "3") (pinfunction "3_3") (pintype "passive"))
      (node (ref "J6") (pin "5") (pinfunction "5_5") (pintype "passive"))
      (node (ref "J6") (pin "7") (pinfunction "7_7") (pintype "passive"))
      (node (ref "J6") (pin "9") (pinfunction "9_9") (pintype "passive"))
      (node (ref "J7") (pin "1") (pinfunction "1_1") (pintype "passive"))
      (node (ref "J7") (pin "11") (pinfunction "11_11") (pintype "passive"))
      (node (ref "J7") (pin "13") (pinfunction "13_13") (pintype "passive"))
      (node (ref "J7") (pin "15") (pinfunction "15_15") (pintype "passive"))
      (node (ref "J7") (pin "3") (pinfunction "3_3") (pintype "passive"))
      (node (ref "J7") (pin "5") (pinfunction "5_5") (pintype "passive"))
      (node (ref "J7") (pin "7") (pinfunction "7_7") (pintype "passive"))
      (node (ref "J7") (pin "9") (pinfunction "9_9") (pintype "passive"))
      (node (ref "J8") (pin "1") (pinfunction "1_1") (pintype "passive"))
      (node (ref "R16") (pin "2") (pinfunction "2_2") (pintype "passive"))
      (node (ref "R20") (pin "2") (pinfunction "2_2") (pintype "passive"))
      (node (ref "R8") (pin "1") (pinfunction "1_1") (pintype "passive"))
      (node (ref "SJ5") (pin "1") (pinfunction "1_1") (pintype "passive"))
      (node (ref "SJ5") (pin "2") (pinfunction "2_2") (pintype "passive"))
      (node (ref "U1") (pin "1") (pinfunction "ADJ_1") (pintype "input"))
      (node (ref "U2") (pin "2") (pinfunction "GND_2") (pintype "input"))
      (node (ref "U4") (pin "P$12") (pinfunction "VSSA_P$12") (pintype "bidirectional"))
      (node (ref "U4") (pin "P$18") (pinfunction "VSS1_P$18") (pintype "bidirectional"))
      (node (ref "U4") (pin "P$63") (pinfunction "VSS2_P$63") (pintype "bidirectional"))
      (node (ref "U5") (pin "16") (pinfunction "FMT_16") (pintype "bidirectional"))
      (node (ref "U5") (pin "19") (pinfunction "DGND_19") (pintype "bidirectional"))
      (node (ref "U5") (pin "3") (pinfunction "CPGND_3") (pintype "bidirectional"))
      (node (ref "U5") (pin "9") (pinfunction "AGND_9") (pintype "bidirectional"))
      (node (ref "U6") (pin "7") (pinfunction "GND_7") (pintype "bidirectional"))
    )
    (net (code "46") (name "Net-(J1-PWR)") (class "Default")
      (node (ref "C1") (pin "1") (pinfunction "1_1") (pintype "passive"))
      (node (ref "J1") (pin "VIN0") (pinfunction "PWR_VIN0") (pintype "bidirectional"))
      (node (ref "U1") (pin "3") (pinfunction "IN_3") (pintype "input"))
    )
    (net (code "47") (name "Net-(J4-Pad3)") (class "Default")
      (node (ref "J4") (pin "3") (pinfunction "3_3") (pintype "passive"))
      (node (ref "SJ2") (pin "1") (pinfunction "1_1") (pintype "passive"))
    )
    (net (code "48") (name "Net-(J4-Pad4)") (class "Default")
      (node (ref "J4") (pin "4") (pinfunction "4_4") (pintype "passive"))
      (node (ref "R15") (pin "2") (pinfunction "2_2") (pintype "passive"))
    )
    (net (code "49") (name "Net-(J6-Pad2)") (class "Default")
      (node (ref "J6") (pin "2") (pinfunction "2_2") (pintype "passive"))
      (node (ref "R11") (pin "1") (pinfunction "1_1") (pintype "passive"))
      (node (ref "R32") (pin "1") (pinfunction "1_1") (pintype "passive"))
    )
    (net (code "50") (name "Net-(J6-Pad4)") (class "Default")
      (node (ref "J6") (pin "4") (pinfunction "4_4") (pintype "passive"))
      (node (ref "R12") (pin "1") (pinfunction "1_1") (pintype "passive"))
      (node (ref "R31") (pin "1") (pinfunction "1_1") (pintype "passive"))
    )
    (net (code "51") (name "Net-(J6-Pad6)") (class "Default")
      (node (ref "J6") (pin "6") (pinfunction "6_6") (pintype "passive"))
      (node (ref "R13") (pin "1") (pinfunction "1_1") (pintype "passive"))
      (node (ref "R30") (pin "1") (pinfunction "1_1") (pintype "passive"))
    )
    (net (code "52") (name "Net-(J6-Pad8)") (class "Default")
      (node (ref "J6") (pin "8") (pinfunction "8_8") (pintype "passive"))
      (node (ref "R18") (pin "1") (pinfunction "1_1") (pintype "passive"))
      (node (ref "R29") (pin "1") (pinfunction "1_1") (pintype "passive"))
    )
    (net (code "53") (name "Net-(J6-Pad10)") (class "Default")
      (node (ref "J6") (pin "10") (pinfunction "10_10") (pintype "passive"))
      (node (ref "R21") (pin "1") (pinfunction "1_1") (pintype "passive"))
      (node (ref "R28") (pin "1") (pinfunction "1_1") (pintype "passive"))
    )
    (net (code "54") (name "Net-(J6-Pad12)") (class "Default")
      (node (ref "J6") (pin "12") (pinfunction "12_12") (pintype "passive"))
      (node (ref "R22") (pin "1") (pinfunction "1_1") (pintype "passive"))
      (node (ref "R27") (pin "1") (pinfunction "1_1") (pintype "passive"))
    )
    (net (code "55") (name "Net-(J6-Pad14)") (class "Default")
      (node (ref "J6") (pin "14") (pinfunction "14_14") (pintype "passive"))
      (node (ref "R23") (pin "1") (pinfunction "1_1") (pintype "passive"))
      (node (ref "R26") (pin "1") (pinfunction "1_1") (pintype "passive"))
    )
    (net (code "56") (name "Net-(J6-Pad16)") (class "Default")
      (node (ref "J6") (pin "16") (pinfunction "16_16") (pintype "passive"))
      (node (ref "R24") (pin "1") (pinfunction "1_1") (pintype "passive"))
      (node (ref "R25") (pin "1") (pinfunction "1_1") (pintype "passive"))
    )
    (net (code "57") (name "Net-(J7-Pad2)") (class "Default")
      (node (ref "J7") (pin "2") (pinfunction "2_2") (pintype "passive"))
      (node (ref "R40") (pin "1") (pinfunction "1_1") (pintype "passive"))
      (node (ref "R48") (pin "1") (pinfunction "1_1") (pintype "passive"))
    )
    (net (code "58") (name "Net-(J7-Pad4)") (class "Default")
      (node (ref "J7") (pin "4") (pinfunction "4_4") (pintype "passive"))
      (node (ref "R39") (pin "1") (pinfunction "1_1") (pintype "passive"))
      (node (ref "R47") (pin "1") (pinfunction "1_1") (pintype "passive"))
    )
    (net (code "59") (name "Net-(J7-Pad6)") (class "Default")
      (node (ref "J7") (pin "6") (pinfunction "6_6") (pintype "passive"))
      (node (ref "R38") (pin "1") (pinfunction "1_1") (pintype "passive"))
      (node (ref "R46") (pin "1") (pinfunction "1_1") (pintype "passive"))
    )
    (net (code "60") (name "Net-(J7-Pad8)") (class "Default")
      (node (ref "J7") (pin "8") (pinfunction "8_8") (pintype "passive"))
      (node (ref "R37") (pin "1") (pinfunction "1_1") (pintype "passive"))
      (node (ref "R45") (pin "1") (pinfunction "1_1") (pintype "passive"))
    )
    (net (code "61") (name "Net-(J7-Pad10)") (class "Default")
      (node (ref "J7") (pin "10") (pinfunction "10_10") (pintype "passive"))
      (node (ref "R36") (pin "1") (pinfunction "1_1") (pintype "passive"))
      (node (ref "R44") (pin "1") (pinfunction "1_1") (pintype "passive"))
    )
    (net (code "62") (name "Net-(J7-Pad12)") (class "Default")
      (node (ref "J7") (pin "12") (pinfunction "12_12") (pintype "passive"))
      (node (ref "R35") (pin "1") (pinfunction "1_1") (pintype "passive"))
      (node (ref "R43") (pin "1") (pinfunction "1_1") (pintype "passive"))
    )
    (net (code "63") (name "Net-(J7-Pad14)") (class "Default")
      (node (ref "J7") (pin "14") (pinfunction "14_14") (pintype "passive"))
      (node (ref "R34") (pin "1") (pinfunction "1_1") (pintype "passive"))
      (node (ref "R42") (pin "1") (pinfunction "1_1") (pintype "passive"))
    )
    (net (code "64") (name "Net-(J7-Pad16)") (class "Default")
      (node (ref "J7") (pin "16") (pinfunction "16_16") (pintype "passive"))
      (node (ref "R33") (pin "1") (pinfunction "1_1") (pintype "passive"))
      (node (ref "R41") (pin "1") (pinfunction "1_1") (pintype "passive"))
    )
    (net (code "65") (name "Net-(JP1-Pad1)") (class "Default")
      (node (ref "JP1") (pin "1") (pinfunction "1_1") (pintype "passive"))
      (node (ref "R16") (pin "1") (pinfunction "1_1") (pintype "passive"))
    )
    (net (code "66") (name "Net-(JP1-Pad3)") (class "Default")
      (node (ref "JP1") (pin "3") (pinfunction "3_3") (pintype "passive"))
      (node (ref "R17") (pin "2") (pinfunction "2_2") (pintype "passive"))
    )
    (net (code "67") (name "Net-(LED1-PadA)") (class "Default")
      (node (ref "LED1") (pin "A") (pinfunction "A_A") (pintype "passive"))
      (node (ref "R19") (pin "2") (pinfunction "2_2") (pintype "passive"))
    )
    (net (code "68") (name "Net-(U2-BP)") (class "Default")
      (node (ref "C4") (pin "1") (pinfunction "1_1") (pintype "passive"))
      (node (ref "U2") (pin "4") (pinfunction "BP_4") (pintype "input"))
    )
    (net (code "69") (name "Net-(U4-PB2-BOOT1)") (class "Default")
      (node (ref "R20") (pin "1") (pinfunction "1_1") (pintype "passive"))
      (node (ref "U4") (pin "P$28") (pinfunction "PB2-BOOT1_P$28") (pintype "bidirectional"))
    )
    (net (code "70") (name "Net-(U4-PH0)") (class "Default")
      (node (ref "C16") (pin "2") (pinfunction "2_2") (pintype "passive"))
      (node (ref "U4") (pin "P$5") (pinfunction "PH0_P$5") (pintype "bidirectional"))
      (node (ref "Y1") (pin "2") (pinfunction "2_2") (pintype "passive"))
    )
    (net (code "71") (name "Net-(U4-PH1)") (class "Default")
      (node (ref "C17") (pin "2") (pinfunction "2_2") (pintype "passive"))
      (node (ref "U4") (pin "P$6") (pinfunction "PH1_P$6") (pintype "bidirectional"))
      (node (ref "Y1") (pin "1") (pinfunction "1_1") (pintype "passive"))
    )
    (net (code "72") (name "Net-(U4-VBAT)") (class "Default")
      (node (ref "C9") (pin "2") (pinfunction "2_2") (pintype "passive"))
      (node (ref "U4") (pin "P$1") (pinfunction "VBAT_P$1") (pintype "bidirectional"))
    )
    (net (code "73") (name "Net-(U4-VCAP1)") (class "Default")
      (node (ref "C14") (pin "1") (pinfunction "1_1") (pintype "passive"))
      (node (ref "U4") (pin "P$31") (pinfunction "VCAP1_P$31") (pintype "bidirectional"))
    )
    (net (code "74") (name "Net-(U4-VCAP2)") (class "Default")
      (node (ref "C20") (pin "1") (pinfunction "1_1") (pintype "passive"))
      (node (ref "U4") (pin "P$47") (pinfunction "VCAP2_P$47") (pintype "bidirectional"))
    )
    (net (code "75") (name "Net-(U5-CAPM)") (class "Default")
      (node (ref "C24") (pin "1") (pinfunction "1_1") (pintype "passive"))
      (node (ref "U5") (pin "4") (pinfunction "CAPM_4") (pintype "bidirectional"))
    )
    (net (code "76") (name "Net-(U5-CAPP)") (class "Default")
      (node (ref "C24") (pin "2") (pinfunction "2_2") (pintype "passive"))
      (node (ref "U5") (pin "2") (pinfunction "CAPP_2") (pintype "bidirectional"))
    )
    (net (code "77") (name "Net-(U5-LDOO)") (class "Default")
      (node (ref "C23") (pin "2") (pinfunction "2_2") (pintype "passive"))
      (node (ref "U5") (pin "18") (pinfunction "LDOO_18") (pintype "bidirectional"))
    )
    (net (code "78") (name "Net-(U5-OUTL)") (class "Default")
      (node (ref "R7") (pin "1") (pinfunction "1_1") (pintype "passive"))
      (node (ref "U5") (pin "6") (pinfunction "OUTL_6") (pintype "bidirectional"))
    )
    (net (code "79") (name "Net-(U5-OUTR)") (class "Default")
      (node (ref "R6") (pin "1") (pinfunction "1_1") (pintype "passive"))
      (node (ref "U5") (pin "7") (pinfunction "OUTR_7") (pintype "bidirectional"))
    )
    (net (code "80") (name "Net-(U5-VNEG)") (class "Default")
      (node (ref "C25") (pin "1") (pinfunction "1_1") (pintype "passive"))
      (node (ref "U5") (pin "5") (pinfunction "VNEG_5") (pintype "bidirectional"))
    )
    (net (code "81") (name "Net-(U6-+IN)") (class "Default")
      (node (ref "C30") (pin "2") (pinfunction "2_2") (pintype "passive"))
      (node (ref "U6") (pin "2") (pinfunction "BYPASS_2") (pintype "bidirectional"))
      (node (ref "U6") (pin "3") (pinfunction "+IN_3") (pintype "bidirectional"))
    )
    (net (code "82") (name "Net-(U6--IN)") (class "Default")
      (node (ref "R10") (pin "1") (pinfunction "1_1") (pintype "passive"))
      (node (ref "R9") (pin "2") (pinfunction "2_2") (pintype "passive"))
      (node (ref "U6") (pin "4") (pinfunction "-IN_4") (pintype "bidirectional"))
    )
    (net (code "83") (name "unconnected-(J4-Pad2)") (class "Default")
      (node (ref "J4") (pin "2") (pinfunction "2_2") (pintype "passive"))
    )
    (net (code "84") (name "unconnected-(J4-Pad6)") (class "Default")
      (node (ref "J4") (pin "6") (pinfunction "6_6") (pintype "passive"))
    )
    (net (code "85") (name "unconnected-(U4-PA8-PadP$41)") (class "Default")
      (node (ref "U4") (pin "P$41") (pinfunction "PA8_P$41") (pintype "bidirectional"))
    )
    (net (code "86") (name "unconnected-(U4-PB1-PadP$27)") (class "Default")
      (node (ref "U4") (pin "P$27") (pinfunction "PB1_P$27") (pintype "bidirectional"))
    )
    (net (code "87") (name "unconnected-(U4-PB3{slash}JTDO-PadP$55)") (class "Default")
      (node (ref "U4") (pin "P$55") (pinfunction "PB3/JTDO_P$55") (pintype "bidirectional"))
    )
    (net (code "88") (name "unconnected-(U4-PB4{slash}JTRST-PadP$56)") (class "Default")
      (node (ref "U4") (pin "P$56") (pinfunction "PB4/JTRST_P$56") (pintype "bidirectional"))
    )
    (net (code "89") (name "unconnected-(U4-PB5-PadP$57)") (class "Default")
      (node (ref "U4") (pin "P$57") (pinfunction "PB5_P$57") (pintype "bidirectional"))
    )
    (net (code "90") (name "unconnected-(U4-PB6-PadP$58)") (class "Default")
      (node (ref "U4") (pin "P$58") (pinfunction "PB6_P$58") (pintype "bidirectional"))
    )
    (net (code "91") (name "unconnected-(U4-PB7-PadP$59)") (class "Default")
      (node (ref "U4") (pin "P$59") (pinfunction "PB7_P$59") (pintype "bidirectional"))
    )
    (net (code "92") (name "unconnected-(U4-PB11-PadP$30)") (class "Default")
      (node (ref "U4") (pin "P$30") (pinfunction "PB11_P$30") (pintype "bidirectional"))
    )
    (net (code "93") (name "unconnected-(U4-PB14{slash}I2S2_XD-PadP$35)") (class "Default")
      (node (ref "U4") (pin "P$35") (pinfunction "PB14/I2S2_XD_P$35") (pintype "bidirectional"))
    )
    (net (code "94") (name "unconnected-(U4-PC7-PadP$38)") (class "Default")
      (node (ref "U4") (pin "P$38") (pinfunction "PC7_P$38") (pintype "bidirectional"))
    )
    (net (code "95") (name "unconnected-(U4-PC13-PadP$2)") (class "Default")
      (node (ref "U4") (pin "P$2") (pinfunction "PC13_P$2") (pintype "bidirectional"))
    )
    (net (code "96") (name "unconnected-(U4-PC14-PadP$3)") (class "Default")
      (node (ref "U4") (pin "P$3") (pinfunction "PC14_P$3") (pintype "bidirectional"))
    )
    (net (code "97") (name "unconnected-(U4-PC15-PadP$4)") (class "Default")
      (node (ref "U4") (pin "P$4") (pinfunction "PC15_P$4") (pintype "bidirectional"))
    )
  )
)
